# bmp_entropia.net
KiCad netlist of a schematic drawn in EAGLE
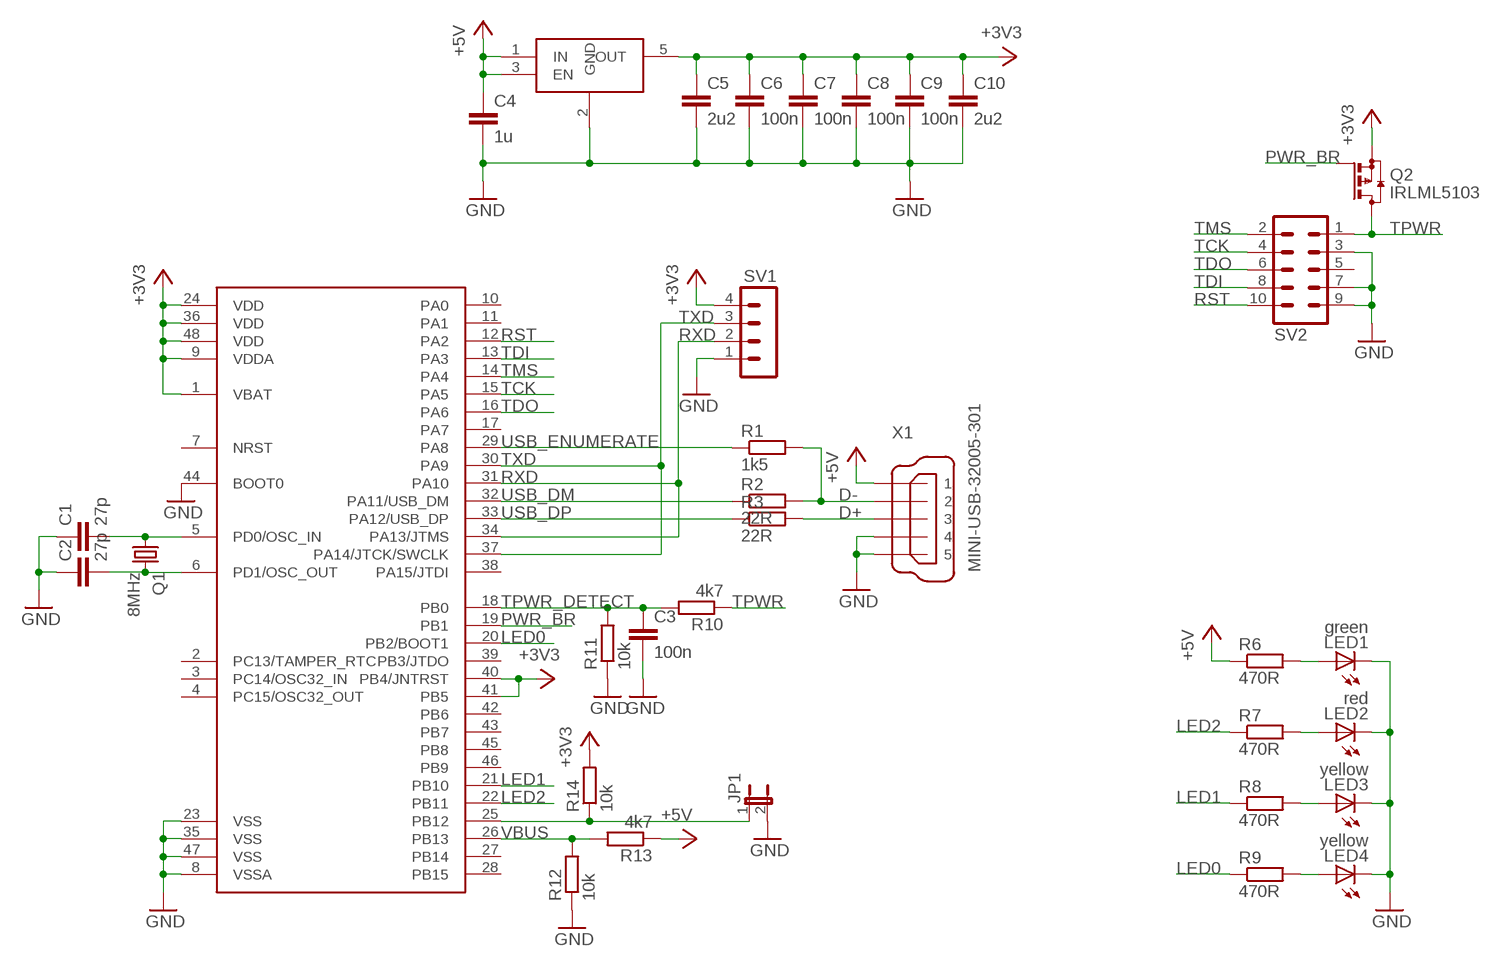
[diagram p0: schematic, sheet 1]

(export (version "E")
  (design (tool "Eeschema 10.0.6"))
  (components
    (comp (ref "C1")
      (value "27p")
      (footprint "eagle-import:C0603")
      (libsource (lib "eagle-import") (part "C-EUC0603"))
    )
    (comp (ref "C2")
      (value "27p")
      (footprint "eagle-import:C0603")
      (libsource (lib "eagle-import") (part "C-EUC0603"))
    )
    (comp (ref "C3")
      (value "100n")
      (footprint "eagle-import:C0603")
      (libsource (lib "eagle-import") (part "C-EUC0603"))
    )
    (comp (ref "C4")
      (value "1u")
      (footprint "eagle-import:C0603")
      (libsource (lib "eagle-import") (part "C-EUC0603"))
    )
    (comp (ref "C5")
      (value "2u2")
      (footprint "eagle-import:C0603")
      (libsource (lib "eagle-import") (part "C-EUC0603"))
    )
    (comp (ref "C6")
      (value "100n")
      (footprint "eagle-import:C0603")
      (libsource (lib "eagle-import") (part "C-EUC0603"))
    )
    (comp (ref "C7")
      (value "100n")
      (footprint "eagle-import:C0603")
      (libsource (lib "eagle-import") (part "C-EUC0603"))
    )
    (comp (ref "C8")
      (value "100n")
      (footprint "eagle-import:C0603")
      (libsource (lib "eagle-import") (part "C-EUC0603"))
    )
    (comp (ref "C9")
      (value "100n")
      (footprint "eagle-import:C0603")
      (libsource (lib "eagle-import") (part "C-EUC0603"))
    )
    (comp (ref "C10")
      (value "2u2")
      (footprint "eagle-import:C0603")
      (libsource (lib "eagle-import") (part "C-EUC0603"))
    )
    (comp (ref "JP1")
      (value "JP1E")
      (footprint "eagle-import:JP1")
      (libsource (lib "eagle-import") (part "JP1E"))
    )
    (comp (ref "LED1")
      (value "green")
      (footprint "eagle-import:CHIPLED_0603")
      (libsource (lib "eagle-import") (part "LEDCHIPLED_0603"))
    )
    (comp (ref "LED2")
      (value "red")
      (footprint "eagle-import:CHIPLED_0603")
      (libsource (lib "eagle-import") (part "LEDCHIPLED_0603"))
    )
    (comp (ref "LED3")
      (value "yellow")
      (footprint "eagle-import:CHIPLED_0603")
      (libsource (lib "eagle-import") (part "LEDCHIPLED_0603"))
    )
    (comp (ref "LED4")
      (value "yellow")
      (footprint "eagle-import:CHIPLED_0603")
      (libsource (lib "eagle-import") (part "LEDCHIPLED_0603"))
    )
    (comp (ref "Q1")
      (value "8MHz")
      (footprint "eagle-import:HC49_S")
      (libsource (lib "eagle-import") (part "CRYSTALHC49S"))
    )
    (comp (ref "Q2")
      (value "IRLML5103")
      (footprint "eagle-import:SOT23")
      (libsource (lib "eagle-import") (part "BSS84"))
    )
    (comp (ref "R1")
      (value "1k5")
      (footprint "eagle-import:R0603")
      (libsource (lib "eagle-import") (part "R-EU_R0603"))
    )
    (comp (ref "R2")
      (value "22R")
      (footprint "eagle-import:R0603")
      (libsource (lib "eagle-import") (part "R-EU_R0603"))
    )
    (comp (ref "R3")
      (value "22R")
      (footprint "eagle-import:R0603")
      (libsource (lib "eagle-import") (part "R-EU_R0603"))
    )
    (comp (ref "R6")
      (value "470R")
      (footprint "eagle-import:R0603")
      (libsource (lib "eagle-import") (part "R-EU_R0603"))
    )
    (comp (ref "R7")
      (value "470R")
      (footprint "eagle-import:R0603")
      (libsource (lib "eagle-import") (part "R-EU_R0603"))
    )
    (comp (ref "R8")
      (value "470R")
      (footprint "eagle-import:R0603")
      (libsource (lib "eagle-import") (part "R-EU_R0603"))
    )
    (comp (ref "R9")
      (value "470R")
      (footprint "eagle-import:R0603")
      (libsource (lib "eagle-import") (part "R-EU_R0603"))
    )
    (comp (ref "R10")
      (value "4k7")
      (footprint "eagle-import:R0603")
      (libsource (lib "eagle-import") (part "R-EU_R0603"))
    )
    (comp (ref "R11")
      (value "10k")
      (footprint "eagle-import:R0603")
      (libsource (lib "eagle-import") (part "R-EU_R0603"))
    )
    (comp (ref "R12")
      (value "10k")
      (footprint "eagle-import:R0603")
      (libsource (lib "eagle-import") (part "R-EU_R0603"))
    )
    (comp (ref "R13")
      (value "4k7")
      (footprint "eagle-import:R0603")
      (libsource (lib "eagle-import") (part "R-EU_R0603"))
    )
    (comp (ref "R14")
      (value "10k")
      (footprint "eagle-import:R0603")
      (libsource (lib "eagle-import") (part "R-EU_R0603"))
    )
    (comp (ref "SV1")
      (value "MA04-1")
      (footprint "eagle-import:MA04-1")
      (libsource (lib "eagle-import") (part "MA04-1"))
    )
    (comp (ref "SV2")
      (value "MA05-2")
      (footprint "eagle-import:MA05-2")
      (libsource (lib "eagle-import") (part "MA05-2"))
    )
    (comp (ref "U$1")
      (value "STM32F_48PIN")
      (footprint "eagle-import:TQFP48")
      (libsource (lib "eagle-import") (part "STM32F_48PIN"))
    )
    (comp (ref "U$2")
      (value "TLV70033DCK")
      (footprint "eagle-import:SC70-5L")
      (libsource (lib "eagle-import") (part "TLV700DCK"))
    )
    (comp (ref "X1")
      (value "MINI-USB-32005-301")
      (footprint "eagle-import:32005-301")
      (libsource (lib "eagle-import") (part "MINI-USB-32005-301"))
    )
  )
  (nets
    (net (code "1") (name "+3V3") (class "Default")
      (node (ref "C10") (pin "1") (pinfunction "1_1") (pintype "passive"))
      (node (ref "C5") (pin "1") (pinfunction "1_1") (pintype "passive"))
      (node (ref "C6") (pin "1") (pinfunction "1_1") (pintype "passive"))
      (node (ref "C7") (pin "1") (pinfunction "1_1") (pintype "passive"))
      (node (ref "C8") (pin "1") (pinfunction "1_1") (pintype "passive"))
      (node (ref "C9") (pin "1") (pinfunction "1_1") (pintype "passive"))
      (node (ref "Q2") (pin "2") (pinfunction "S_2") (pintype "passive"))
      (node (ref "R14") (pin "2") (pinfunction "2_2") (pintype "passive"))
      (node (ref "SV1") (pin "4") (pinfunction "4_4") (pintype "passive"))
      (node (ref "U$1") (pin "1") (pinfunction "VBAT_1") (pintype "bidirectional"))
      (node (ref "U$1") (pin "24") (pinfunction "VDD_24") (pintype "bidirectional"))
      (node (ref "U$1") (pin "36") (pinfunction "VDD_36") (pintype "bidirectional"))
      (node (ref "U$1") (pin "40") (pinfunction "PB4/JNTRST_40") (pintype "bidirectional"))
      (node (ref "U$1") (pin "41") (pinfunction "PB5_41") (pintype "bidirectional"))
      (node (ref "U$1") (pin "48") (pinfunction "VDD_48") (pintype "bidirectional"))
      (node (ref "U$1") (pin "9") (pinfunction "VDDA_9") (pintype "bidirectional"))
      (node (ref "U$2") (pin "5") (pinfunction "OUT_5") (pintype "bidirectional"))
    )
    (net (code "2") (name "+5V") (class "Default")
      (node (ref "C4") (pin "1") (pinfunction "1_1") (pintype "passive"))
      (node (ref "R13") (pin "1") (pinfunction "1_1") (pintype "passive"))
      (node (ref "R6") (pin "1") (pinfunction "1_1") (pintype "passive"))
      (node (ref "U$2") (pin "1") (pinfunction "IN_1") (pintype "bidirectional"))
      (node (ref "U$2") (pin "3") (pinfunction "EN_3") (pintype "bidirectional"))
      (node (ref "X1") (pin "1") (pinfunction "1_1") (pintype "passive"))
    )
    (net (code "3") (name "/D+") (class "Default")
      (node (ref "R3") (pin "2") (pinfunction "2_2") (pintype "passive"))
      (node (ref "X1") (pin "3") (pinfunction "3_3") (pintype "passive"))
    )
    (net (code "4") (name "/D-") (class "Default")
      (node (ref "R1") (pin "2") (pinfunction "2_2") (pintype "passive"))
      (node (ref "R2") (pin "2") (pinfunction "2_2") (pintype "passive"))
      (node (ref "X1") (pin "2") (pinfunction "2_2") (pintype "passive"))
    )
    (net (code "5") (name "/LED0") (class "Default")
      (node (ref "R9") (pin "1") (pinfunction "1_1") (pintype "passive"))
      (node (ref "U$1") (pin "20") (pinfunction "PB2/BOOT1_20") (pintype "bidirectional"))
    )
    (net (code "6") (name "/LED1") (class "Default")
      (node (ref "R8") (pin "1") (pinfunction "1_1") (pintype "passive"))
      (node (ref "U$1") (pin "21") (pinfunction "PB10_21") (pintype "bidirectional"))
    )
    (net (code "7") (name "/LED2") (class "Default")
      (node (ref "R7") (pin "1") (pinfunction "1_1") (pintype "passive"))
      (node (ref "U$1") (pin "22") (pinfunction "PB11_22") (pintype "bidirectional"))
    )
    (net (code "8") (name "/PWR_BR") (class "Default")
      (node (ref "Q2") (pin "1") (pinfunction "G_1") (pintype "passive"))
      (node (ref "U$1") (pin "19") (pinfunction "PB1_19") (pintype "bidirectional"))
    )
    (net (code "9") (name "/RST") (class "Default")
      (node (ref "SV2") (pin "10") (pinfunction "10_10") (pintype "passive"))
      (node (ref "U$1") (pin "12") (pinfunction "PA2_12") (pintype "bidirectional"))
    )
    (net (code "10") (name "/RXD") (class "Default")
      (node (ref "SV1") (pin "2") (pinfunction "2_2") (pintype "passive"))
      (node (ref "U$1") (pin "31") (pinfunction "PA10_31") (pintype "bidirectional"))
      (node (ref "U$1") (pin "34") (pinfunction "PA13/JTMS_34") (pintype "bidirectional"))
    )
    (net (code "11") (name "/TCK") (class "Default")
      (node (ref "SV2") (pin "4") (pinfunction "4_4") (pintype "passive"))
      (node (ref "U$1") (pin "15") (pinfunction "PA5_15") (pintype "bidirectional"))
    )
    (net (code "12") (name "/TDI") (class "Default")
      (node (ref "SV2") (pin "8") (pinfunction "8_8") (pintype "passive"))
      (node (ref "U$1") (pin "13") (pinfunction "PA3_13") (pintype "bidirectional"))
    )
    (net (code "13") (name "/TDO") (class "Default")
      (node (ref "SV2") (pin "6") (pinfunction "6_6") (pintype "passive"))
      (node (ref "U$1") (pin "16") (pinfunction "PA6_16") (pintype "bidirectional"))
    )
    (net (code "14") (name "/TMS") (class "Default")
      (node (ref "SV2") (pin "2") (pinfunction "2_2") (pintype "passive"))
      (node (ref "U$1") (pin "14") (pinfunction "PA4_14") (pintype "bidirectional"))
    )
    (net (code "15") (name "/TPWR") (class "Default")
      (node (ref "Q2") (pin "3") (pinfunction "D_3") (pintype "passive"))
      (node (ref "R10") (pin "1") (pinfunction "1_1") (pintype "passive"))
      (node (ref "SV2") (pin "1") (pinfunction "1_1") (pintype "passive"))
    )
    (net (code "16") (name "/TPWR_DETECT") (class "Default")
      (node (ref "C3") (pin "1") (pinfunction "1_1") (pintype "passive"))
      (node (ref "R10") (pin "2") (pinfunction "2_2") (pintype "passive"))
      (node (ref "R11") (pin "2") (pinfunction "2_2") (pintype "passive"))
      (node (ref "U$1") (pin "18") (pinfunction "PB0_18") (pintype "bidirectional"))
    )
    (net (code "17") (name "/TXD") (class "Default")
      (node (ref "SV1") (pin "3") (pinfunction "3_3") (pintype "passive"))
      (node (ref "U$1") (pin "30") (pinfunction "PA9_30") (pintype "bidirectional"))
      (node (ref "U$1") (pin "37") (pinfunction "PA14/JTCK/SWCLK_37") (pintype "bidirectional"))
    )
    (net (code "18") (name "/USB_DM") (class "Default")
      (node (ref "R2") (pin "1") (pinfunction "1_1") (pintype "passive"))
      (node (ref "U$1") (pin "32") (pinfunction "PA11/USB_DM_32") (pintype "bidirectional"))
    )
    (net (code "19") (name "/USB_DP") (class "Default")
      (node (ref "R3") (pin "1") (pinfunction "1_1") (pintype "passive"))
      (node (ref "U$1") (pin "33") (pinfunction "PA12/USB_DP_33") (pintype "bidirectional"))
    )
    (net (code "20") (name "/USB_ENUMERATE") (class "Default")
      (node (ref "R1") (pin "1") (pinfunction "1_1") (pintype "passive"))
      (node (ref "U$1") (pin "29") (pinfunction "PA8_29") (pintype "bidirectional"))
    )
    (net (code "21") (name "/VBUS") (class "Default")
      (node (ref "R12") (pin "2") (pinfunction "2_2") (pintype "passive"))
      (node (ref "R13") (pin "2") (pinfunction "2_2") (pintype "passive"))
      (node (ref "U$1") (pin "26") (pinfunction "PB13_26") (pintype "bidirectional"))
    )
    (net (code "22") (name "GND") (class "Default")
      (node (ref "C1") (pin "1") (pinfunction "1_1") (pintype "passive"))
      (node (ref "C10") (pin "2") (pinfunction "2_2") (pintype "passive"))
      (node (ref "C2") (pin "1") (pinfunction "1_1") (pintype "passive"))
      (node (ref "C3") (pin "2") (pinfunction "2_2") (pintype "passive"))
      (node (ref "C4") (pin "2") (pinfunction "2_2") (pintype "passive"))
      (node (ref "C5") (pin "2") (pinfunction "2_2") (pintype "passive"))
      (node (ref "C6") (pin "2") (pinfunction "2_2") (pintype "passive"))
      (node (ref "C7") (pin "2") (pinfunction "2_2") (pintype "passive"))
      (node (ref "C8") (pin "2") (pinfunction "2_2") (pintype "passive"))
      (node (ref "C9") (pin "2") (pinfunction "2_2") (pintype "passive"))
      (node (ref "JP1") (pin "2") (pinfunction "2_2") (pintype "passive"))
      (node (ref "LED1") (pin "C") (pinfunction "C_C") (pintype "passive"))
      (node (ref "LED2") (pin "C") (pinfunction "C_C") (pintype "passive"))
      (node (ref "LED3") (pin "C") (pinfunction "C_C") (pintype "passive"))
      (node (ref "LED4") (pin "C") (pinfunction "C_C") (pintype "passive"))
      (node (ref "R11") (pin "1") (pinfunction "1_1") (pintype "passive"))
      (node (ref "R12") (pin "1") (pinfunction "1_1") (pintype "passive"))
      (node (ref "SV1") (pin "1") (pinfunction "1_1") (pintype "passive"))
      (node (ref "SV2") (pin "3") (pinfunction "3_3") (pintype "passive"))
      (node (ref "SV2") (pin "7") (pinfunction "7_7") (pintype "passive"))
      (node (ref "SV2") (pin "9") (pinfunction "9_9") (pintype "passive"))
      (node (ref "U$1") (pin "23") (pinfunction "VSS_23") (pintype "bidirectional"))
      (node (ref "U$1") (pin "35") (pinfunction "VSS_35") (pintype "bidirectional"))
      (node (ref "U$1") (pin "44") (pinfunction "BOOT0_44") (pintype "bidirectional"))
      (node (ref "U$1") (pin "47") (pinfunction "VSS_47") (pintype "bidirectional"))
      (node (ref "U$1") (pin "8") (pinfunction "VSSA_8") (pintype "bidirectional"))
      (node (ref "U$2") (pin "2") (pinfunction "GND_2") (pintype "bidirectional"))
      (node (ref "X1") (pin "4") (pinfunction "4_4") (pintype "passive"))
      (node (ref "X1") (pin "5") (pinfunction "5_5") (pintype "passive"))
    )
    (net (code "23") (name "Net-(LED1-PadA)") (class "Default")
      (node (ref "LED1") (pin "A") (pinfunction "A_A") (pintype "passive"))
      (node (ref "R6") (pin "2") (pinfunction "2_2") (pintype "passive"))
    )
    (net (code "24") (name "Net-(LED2-PadA)") (class "Default")
      (node (ref "LED2") (pin "A") (pinfunction "A_A") (pintype "passive"))
      (node (ref "R7") (pin "2") (pinfunction "2_2") (pintype "passive"))
    )
    (net (code "25") (name "Net-(LED3-PadA)") (class "Default")
      (node (ref "LED3") (pin "A") (pinfunction "A_A") (pintype "passive"))
      (node (ref "R8") (pin "2") (pinfunction "2_2") (pintype "passive"))
    )
    (net (code "26") (name "Net-(LED4-PadA)") (class "Default")
      (node (ref "LED4") (pin "A") (pinfunction "A_A") (pintype "passive"))
      (node (ref "R9") (pin "2") (pinfunction "2_2") (pintype "passive"))
    )
    (net (code "27") (name "Net-(U$1-PB12)") (class "Default")
      (node (ref "JP1") (pin "1") (pinfunction "1_1") (pintype "passive"))
      (node (ref "R14") (pin "1") (pinfunction "1_1") (pintype "passive"))
      (node (ref "U$1") (pin "25") (pinfunction "PB12_25") (pintype "bidirectional"))
    )
    (net (code "28") (name "Net-(U$1-PD0{slash}OSC_IN)") (class "Default")
      (node (ref "C1") (pin "2") (pinfunction "2_2") (pintype "passive"))
      (node (ref "Q1") (pin "1") (pinfunction "1_1") (pintype "passive"))
      (node (ref "U$1") (pin "5") (pinfunction "PD0/OSC_IN_5") (pintype "bidirectional"))
    )
    (net (code "29") (name "Net-(U$1-PD1{slash}OSC_OUT)") (class "Default")
      (node (ref "C2") (pin "2") (pinfunction "2_2") (pintype "passive"))
      (node (ref "Q1") (pin "2") (pinfunction "2_2") (pintype "passive"))
      (node (ref "U$1") (pin "6") (pinfunction "PD1/OSC_OUT_6") (pintype "bidirectional"))
    )
    (net (code "30") (name "unconnected-(SV2-Pad5)") (class "Default")
      (node (ref "SV2") (pin "5") (pinfunction "5_5") (pintype "passive"))
    )
    (net (code "31") (name "unconnected-(U$1-NRST-Pad7)") (class "Default")
      (node (ref "U$1") (pin "7") (pinfunction "NRST_7") (pintype "bidirectional"))
    )
    (net (code "32") (name "unconnected-(U$1-PA0-Pad10)") (class "Default")
      (node (ref "U$1") (pin "10") (pinfunction "PA0_10") (pintype "bidirectional"))
    )
    (net (code "33") (name "unconnected-(U$1-PA1-Pad11)") (class "Default")
      (node (ref "U$1") (pin "11") (pinfunction "PA1_11") (pintype "bidirectional"))
    )
    (net (code "34") (name "unconnected-(U$1-PA7-Pad17)") (class "Default")
      (node (ref "U$1") (pin "17") (pinfunction "PA7_17") (pintype "bidirectional"))
    )
    (net (code "35") (name "unconnected-(U$1-PA15{slash}JTDI-Pad38)") (class "Default")
      (node (ref "U$1") (pin "38") (pinfunction "PA15/JTDI_38") (pintype "bidirectional"))
    )
    (net (code "36") (name "unconnected-(U$1-PB3{slash}JTDO-Pad39)") (class "Default")
      (node (ref "U$1") (pin "39") (pinfunction "PB3/JTDO_39") (pintype "bidirectional"))
    )
    (net (code "37") (name "unconnected-(U$1-PB6-Pad42)") (class "Default")
      (node (ref "U$1") (pin "42") (pinfunction "PB6_42") (pintype "bidirectional"))
    )
    (net (code "38") (name "unconnected-(U$1-PB7-Pad43)") (class "Default")
      (node (ref "U$1") (pin "43") (pinfunction "PB7_43") (pintype "bidirectional"))
    )
    (net (code "39") (name "unconnected-(U$1-PB8-Pad45)") (class "Default")
      (node (ref "U$1") (pin "45") (pinfunction "PB8_45") (pintype "bidirectional"))
    )
    (net (code "40") (name "unconnected-(U$1-PB9-Pad46)") (class "Default")
      (node (ref "U$1") (pin "46") (pinfunction "PB9_46") (pintype "bidirectional"))
    )
    (net (code "41") (name "unconnected-(U$1-PB14-Pad27)") (class "Default")
      (node (ref "U$1") (pin "27") (pinfunction "PB14_27") (pintype "bidirectional"))
    )
    (net (code "42") (name "unconnected-(U$1-PB15-Pad28)") (class "Default")
      (node (ref "U$1") (pin "28") (pinfunction "PB15_28") (pintype "bidirectional"))
    )
    (net (code "43") (name "unconnected-(U$1-PC13{slash}TAMPER_RTC-Pad2)") (class "Default")
      (node (ref "U$1") (pin "2") (pinfunction "PC13/TAMPER_RTC_2") (pintype "bidirectional"))
    )
    (net (code "44") (name "unconnected-(U$1-PC14{slash}OSC32_IN-Pad3)") (class "Default")
      (node (ref "U$1") (pin "3") (pinfunction "PC14/OSC32_IN_3") (pintype "bidirectional"))
    )
    (net (code "45") (name "unconnected-(U$1-PC15{slash}OSC32_OUT-Pad4)") (class "Default")
      (node (ref "U$1") (pin "4") (pinfunction "PC15/OSC32_OUT_4") (pintype "bidirectional"))
    )
  )
)
